# aq_mx_v1-4-0c.net
KiCad netlist of a schematic drawn in EAGLE
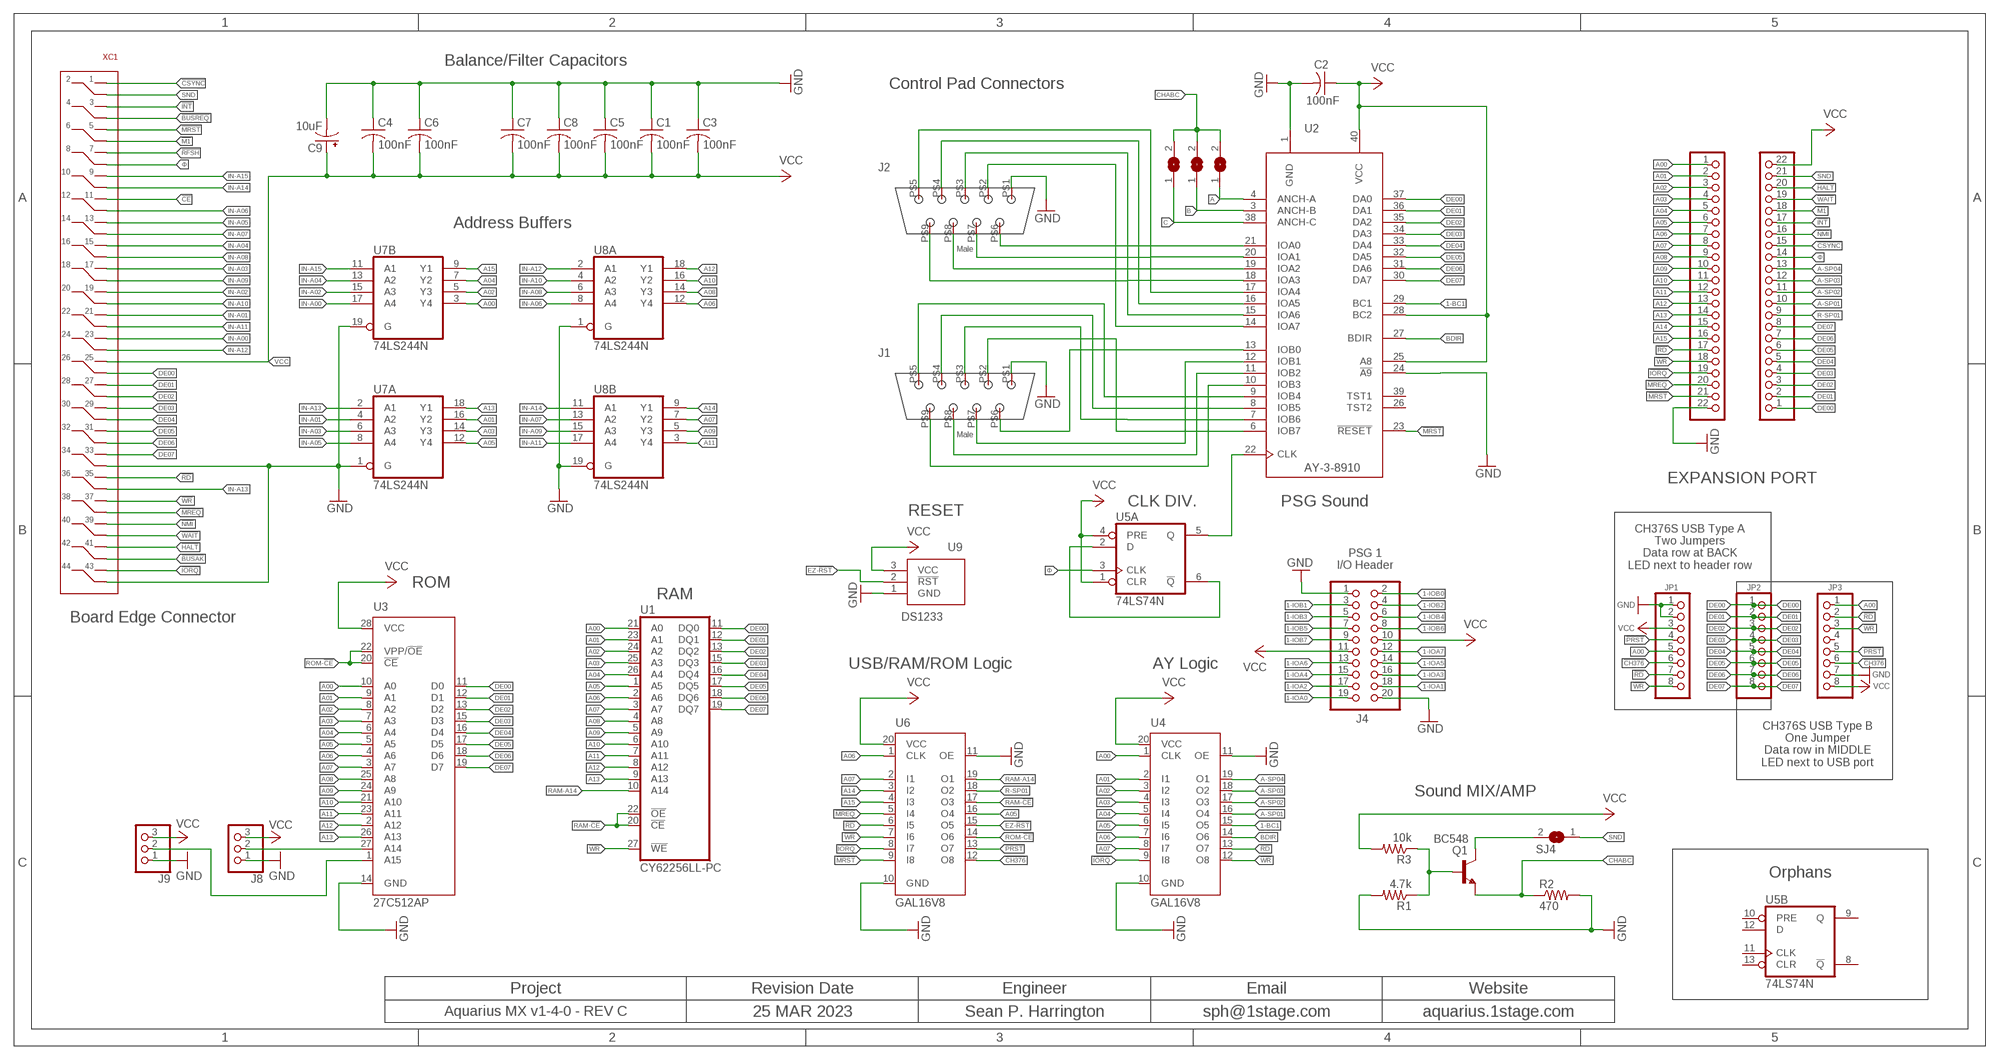
[diagram p0: schematic, sheet 1]

(export (version "E")
  (design (tool "Eeschema 10.0.6"))
  (components
    (comp (ref "C1")
      (value "100nF")
      (footprint "eagle-import:C050-025X075")
      (libsource (lib "eagle-import") (part "C-US050-025X075"))
    )
    (comp (ref "C2")
      (value "100nF")
      (footprint "eagle-import:C050-025X075")
      (libsource (lib "eagle-import") (part "C-US050-025X075"))
    )
    (comp (ref "C3")
      (value "100nF")
      (footprint "eagle-import:C050-025X075")
      (libsource (lib "eagle-import") (part "C-US050-025X075"))
    )
    (comp (ref "C4")
      (value "100nF")
      (footprint "eagle-import:C050-025X075")
      (libsource (lib "eagle-import") (part "C-US050-025X075"))
    )
    (comp (ref "C5")
      (value "100nF")
      (footprint "eagle-import:C050-025X075")
      (libsource (lib "eagle-import") (part "C-US050-025X075"))
    )
    (comp (ref "C6")
      (value "100nF")
      (footprint "eagle-import:C050-025X075")
      (libsource (lib "eagle-import") (part "C-US050-025X075"))
    )
    (comp (ref "C7")
      (value "100nF")
      (footprint "eagle-import:C050-025X075")
      (libsource (lib "eagle-import") (part "C-US050-025X075"))
    )
    (comp (ref "C8")
      (value "100nF")
      (footprint "eagle-import:C050-025X075")
      (libsource (lib "eagle-import") (part "C-US050-025X075"))
    )
    (comp (ref "C9")
      (value "10uF")
      (footprint "eagle-import:E22-6")
      (libsource (lib "eagle-import") (part "CPOL-USE22-6AXIAL"))
    )
    (comp (ref "J1")
      (value "DB9-MALE-RA")
      (footprint "eagle-import:DB9-MALE-RA")
      (libsource (lib "eagle-import") (part "DB9-MALE-RA"))
    )
    (comp (ref "J2")
      (value "DB9-MALE-RA")
      (footprint "eagle-import:DB9-MALE-RA")
      (libsource (lib "eagle-import") (part "DB9-MALE-RA"))
    )
    (comp (ref "J4")
      (value "PINHD-2X10")
      (footprint "eagle-import:2X10")
      (libsource (lib "eagle-import") (part "PINHD-2X10"))
    )
    (comp (ref "J6")
      (value "PINHD-1X22")
      (footprint "eagle-import:1X22")
      (libsource (lib "eagle-import") (part "PINHD-1X22"))
    )
    (comp (ref "J7")
      (value "PINHD-1X22")
      (footprint "eagle-import:1X22")
      (libsource (lib "eagle-import") (part "PINHD-1X22"))
    )
    (comp (ref "J8")
      (value "PINHD-1X3")
      (footprint "eagle-import:1X03")
      (libsource (lib "eagle-import") (part "PINHD-1X3"))
    )
    (comp (ref "J9")
      (value "PINHD-1X3")
      (footprint "eagle-import:1X03")
      (libsource (lib "eagle-import") (part "PINHD-1X3"))
    )
    (comp (ref "JP1")
      (value "PINHD-1X8")
      (footprint "eagle-import:1X08")
      (libsource (lib "eagle-import") (part "PINHD-1X8"))
    )
    (comp (ref "JP2")
      (value "PINHD-1X8")
      (footprint "eagle-import:1X08")
      (libsource (lib "eagle-import") (part "PINHD-1X8"))
    )
    (comp (ref "JP3")
      (value "PINHD-1X8")
      (footprint "eagle-import:1X08")
      (libsource (lib "eagle-import") (part "PINHD-1X8"))
    )
    (comp (ref "Q1")
      (value "BC548")
      (footprint "eagle-import:TO92-CBE")
      (libsource (lib "eagle-import") (part "-NPN-TO92-CBEBC548"))
    )
    (comp (ref "R1")
      (value "4.7k")
      (footprint "eagle-import:0204_7")
      (libsource (lib "eagle-import") (part "R-US_0204/7"))
    )
    (comp (ref "R2")
      (value "470")
      (footprint "eagle-import:0204_7")
      (libsource (lib "eagle-import") (part "R-US_0204/7"))
    )
    (comp (ref "R3")
      (value "10k")
      (footprint "eagle-import:0204_7")
      (libsource (lib "eagle-import") (part "R-US_0204/7"))
    )
    (comp (ref "SJ1") (value "SJ") (footprint "eagle-import:SJ") (libsource (lib "eagle-import") (part "SJ")))
    (comp (ref "SJ2") (value "SJ") (footprint "eagle-import:SJ") (libsource (lib "eagle-import") (part "SJ")))
    (comp (ref "SJ3") (value "SJ") (footprint "eagle-import:SJ") (libsource (lib "eagle-import") (part "SJ")))
    (comp (ref "SJ4") (value "SJ") (footprint "eagle-import:SJ") (libsource (lib "eagle-import") (part "SJ")))
    (comp (ref "U1")
      (value "CY62256LL-PC")
      (footprint "eagle-import:DIL28-6")
      (libsource (lib "eagle-import") (part "CY62256LL-?PC"))
    )
    (comp (ref "U2")
      (value "AY-3-8910")
      (footprint "eagle-import:RAD38910-DIL40-6")
      (libsource (lib "eagle-import") (part "RAD38910DIL40-6"))
    )
    (comp (ref "U3")
      (value "27C512AP")
      (footprint "eagle-import:DIL28-6")
      (fields (field (name "MPN") "M27C512-90B6"))
      (libsource (lib "eagle-import") (part "27512APC"))
    )
    (comp (ref "U4")
      (value "GAL16V8")
      (footprint "eagle-import:DIL20")
      (fields (field (name "MPN") "ATF16V8CZ-15PU"))
      (libsource (lib "eagle-import") (part "ATF16V8BP3"))
    )
    (comp (ref "U5")
      (value "74LS74N")
      (footprint "eagle-import:DIL14")
      (libsource (lib "eagle-import") (part "7474NLS"))
    )
    (comp (ref "U6")
      (value "GAL16V8")
      (footprint "eagle-import:DIL20")
      (fields (field (name "MPN") "ATF16V8CZ-15PU"))
      (libsource (lib "eagle-import") (part "ATF16V8BP3"))
    )
    (comp (ref "U7")
      (value "74LS244N")
      (footprint "eagle-import:DIL20")
      (libsource (lib "eagle-import") (part "74244NLS"))
    )
    (comp (ref "U8")
      (value "74LS244N")
      (footprint "eagle-import:DIL20")
      (libsource (lib "eagle-import") (part "74244NLS"))
    )
    (comp (ref "U9")
      (value "DS1233")
      (footprint "eagle-import:TO-92")
      (fields
        (field (name "ARROW_PART_NUMBER") "DS1233-10+")
        (field (name "MOUSER_PART_NUMBER") "700-DS1233-10")
      )
      (libsource (lib "eagle-import") (part "DS1233-10+"))
    )
    (comp (ref "XC1")
      (value "AQ-CART-EDGE")
      (footprint "eagle-import:AQ-CART-EDGE")
      (libsource (lib "eagle-import") (part "AQ-CART-EDGE"))
    )
  )
  (nets
    (net (code "1") (name "/EZ-~{RST}") (class "Default")
      (node (ref "U6") (pin "15") (pinfunction "O5_15") (pintype "output"))
      (node (ref "U9") (pin "2") (pinfunction "~{RST}_2") (pintype "input"))
    )
    (net (code "2") (name "/RAM-~{CE}") (class "Default")
      (node (ref "U1") (pin "20") (pinfunction "~{CE}_20") (pintype "input"))
      (node (ref "U1") (pin "22") (pinfunction "~{OE}_22") (pintype "input"))
      (node (ref "U6") (pin "17") (pinfunction "O3_17") (pintype "output"))
    )
    (net (code "3") (name "/ROM-~{CE}") (class "Default")
      (node (ref "U3") (pin "20") (pinfunction "~{CE}_20") (pintype "input"))
      (node (ref "U3") (pin "22") (pinfunction "VPP/~{OE}_22") (pintype "input"))
      (node (ref "U6") (pin "14") (pinfunction "O6_14") (pintype "output"))
    )
    (net (code "4") (name "/~{BUSAK}") (class "Default")
      (node (ref "XC1") (pin "P$42") (pinfunction "X42_P$42") (pintype "bidirectional"))
    )
    (net (code "5") (name "/~{BUSREQ}") (class "Default")
      (node (ref "XC1") (pin "P$4") (pinfunction "X4_P$4") (pintype "bidirectional"))
    )
    (net (code "6") (name "/~{CE}") (class "Default")
      (node (ref "XC1") (pin "P$11") (pinfunction "X11_P$11") (pintype "bidirectional"))
    )
    (net (code "7") (name "/~{CH376}") (class "Default")
      (node (ref "JP1") (pin "6") (pinfunction "6_6") (pintype "passive"))
      (node (ref "JP3") (pin "6") (pinfunction "6_6") (pintype "passive"))
      (node (ref "U6") (pin "12") (pinfunction "O8_12") (pintype "output"))
    )
    (net (code "8") (name "/~{CSYNC}") (class "Default")
      (node (ref "J6") (pin "15") (pinfunction "15_15") (pintype "passive"))
      (node (ref "XC1") (pin "P$1") (pinfunction "X1_P$1") (pintype "bidirectional"))
    )
    (net (code "9") (name "/~{HALT}") (class "Default")
      (node (ref "J6") (pin "20") (pinfunction "20_20") (pintype "passive"))
      (node (ref "XC1") (pin "P$41") (pinfunction "X41_P$41") (pintype "bidirectional"))
    )
    (net (code "10") (name "/~{INT}") (class "Default")
      (node (ref "J6") (pin "17") (pinfunction "17_17") (pintype "passive"))
      (node (ref "XC1") (pin "P$3") (pinfunction "X3_P$3") (pintype "bidirectional"))
    )
    (net (code "11") (name "/~{IORQ}") (class "Default")
      (node (ref "J7") (pin "19") (pinfunction "19_19") (pintype "passive"))
      (node (ref "U4") (pin "9") (pinfunction "I8_9") (pintype "input"))
      (node (ref "U6") (pin "8") (pinfunction "I7_8") (pintype "input"))
      (node (ref "XC1") (pin "P$43") (pinfunction "X43_P$43") (pintype "bidirectional"))
    )
    (net (code "12") (name "/~{M1}") (class "Default")
      (node (ref "J6") (pin "18") (pinfunction "18_18") (pintype "passive"))
      (node (ref "XC1") (pin "P$6") (pinfunction "X6_P$6") (pintype "bidirectional"))
    )
    (net (code "13") (name "/~{MREQ}") (class "Default")
      (node (ref "J7") (pin "20") (pinfunction "20_20") (pintype "passive"))
      (node (ref "U6") (pin "5") (pinfunction "I4_5") (pintype "input"))
      (node (ref "XC1") (pin "P$38") (pinfunction "X38_P$38") (pintype "bidirectional"))
    )
    (net (code "14") (name "/~{MRST}") (class "Default")
      (node (ref "J7") (pin "21") (pinfunction "21_21") (pintype "passive"))
      (node (ref "U2") (pin "23") (pinfunction "~{RESET}_23") (pintype "bidirectional"))
      (node (ref "U6") (pin "9") (pinfunction "I8_9") (pintype "input"))
      (node (ref "XC1") (pin "P$5") (pinfunction "X5_P$5") (pintype "bidirectional"))
    )
    (net (code "15") (name "/~{NMI}") (class "Default")
      (node (ref "J6") (pin "16") (pinfunction "16_16") (pintype "passive"))
      (node (ref "XC1") (pin "P$39") (pinfunction "X39_P$39") (pintype "bidirectional"))
    )
    (net (code "16") (name "/~{PRST}") (class "Default")
      (node (ref "JP1") (pin "4") (pinfunction "4_4") (pintype "passive"))
      (node (ref "JP3") (pin "5") (pinfunction "5_5") (pintype "passive"))
      (node (ref "U6") (pin "13") (pinfunction "O7_13") (pintype "output"))
    )
    (net (code "17") (name "/~{RD}") (class "Default")
      (node (ref "J7") (pin "17") (pinfunction "17_17") (pintype "passive"))
      (node (ref "JP1") (pin "7") (pinfunction "7_7") (pintype "passive"))
      (node (ref "JP3") (pin "2") (pinfunction "2_2") (pintype "passive"))
      (node (ref "U4") (pin "13") (pinfunction "O7_13") (pintype "output"))
      (node (ref "U6") (pin "6") (pinfunction "I5_6") (pintype "input"))
      (node (ref "XC1") (pin "P$35") (pinfunction "X35_P$35") (pintype "bidirectional"))
    )
    (net (code "18") (name "/~{RFSH}") (class "Default")
      (node (ref "XC1") (pin "P$7") (pinfunction "X7_P$7") (pintype "bidirectional"))
    )
    (net (code "19") (name "/~{WAIT}") (class "Default")
      (node (ref "J6") (pin "19") (pinfunction "19_19") (pintype "passive"))
      (node (ref "XC1") (pin "P$40") (pinfunction "X40_P$40") (pintype "bidirectional"))
    )
    (net (code "20") (name "/~{WR}") (class "Default")
      (node (ref "J7") (pin "18") (pinfunction "18_18") (pintype "passive"))
      (node (ref "JP1") (pin "8") (pinfunction "8_8") (pintype "passive"))
      (node (ref "JP3") (pin "3") (pinfunction "3_3") (pintype "passive"))
      (node (ref "U1") (pin "27") (pinfunction "~{WE}_27") (pintype "input"))
      (node (ref "U4") (pin "12") (pinfunction "O8_12") (pintype "output"))
      (node (ref "U6") (pin "7") (pinfunction "I6_7") (pintype "input"))
      (node (ref "XC1") (pin "P$37") (pinfunction "X37_P$37") (pintype "bidirectional"))
    )
    (net (code "21") (name "1-BC1") (class "Default")
      (node (ref "U2") (pin "29") (pinfunction "BC1_29") (pintype "bidirectional"))
      (node (ref "U4") (pin "15") (pinfunction "O5_15") (pintype "output"))
    )
    (net (code "22") (name "1-IOA0") (class "Default")
      (node (ref "J2") (pin "P$6") (pinfunction "P$6_P$6") (pintype "bidirectional"))
      (node (ref "J4") (pin "19") (pinfunction "19_19") (pintype "passive"))
      (node (ref "U2") (pin "21") (pinfunction "IOA0_21") (pintype "bidirectional"))
    )
    (net (code "23") (name "1-IOA1") (class "Default")
      (node (ref "J2") (pin "P$7") (pinfunction "P$7_P$7") (pintype "bidirectional"))
      (node (ref "J4") (pin "18") (pinfunction "18_18") (pintype "passive"))
      (node (ref "U2") (pin "20") (pinfunction "IOA1_20") (pintype "bidirectional"))
    )
    (net (code "24") (name "1-IOA2") (class "Default")
      (node (ref "J2") (pin "P$8") (pinfunction "P$8_P$8") (pintype "bidirectional"))
      (node (ref "J4") (pin "17") (pinfunction "17_17") (pintype "passive"))
      (node (ref "U2") (pin "19") (pinfunction "IOA2_19") (pintype "bidirectional"))
    )
    (net (code "25") (name "1-IOA3") (class "Default")
      (node (ref "J2") (pin "P$9") (pinfunction "P$9_P$9") (pintype "bidirectional"))
      (node (ref "J4") (pin "16") (pinfunction "16_16") (pintype "passive"))
      (node (ref "U2") (pin "18") (pinfunction "IOA3_18") (pintype "bidirectional"))
    )
    (net (code "26") (name "1-IOA4") (class "Default")
      (node (ref "J2") (pin "P$5") (pinfunction "P$5_P$5") (pintype "bidirectional"))
      (node (ref "J4") (pin "15") (pinfunction "15_15") (pintype "passive"))
      (node (ref "U2") (pin "17") (pinfunction "IOA4_17") (pintype "bidirectional"))
    )
    (net (code "27") (name "1-IOA5") (class "Default")
      (node (ref "J2") (pin "P$4") (pinfunction "P$4_P$4") (pintype "bidirectional"))
      (node (ref "J4") (pin "14") (pinfunction "14_14") (pintype "passive"))
      (node (ref "U2") (pin "16") (pinfunction "IOA5_16") (pintype "bidirectional"))
    )
    (net (code "28") (name "1-IOA6") (class "Default")
      (node (ref "J2") (pin "P$3") (pinfunction "P$3_P$3") (pintype "bidirectional"))
      (node (ref "J4") (pin "13") (pinfunction "13_13") (pintype "passive"))
      (node (ref "U2") (pin "15") (pinfunction "IOA6_15") (pintype "bidirectional"))
    )
    (net (code "29") (name "1-IOA7") (class "Default")
      (node (ref "J2") (pin "P$2") (pinfunction "P$2_P$2") (pintype "bidirectional"))
      (node (ref "J4") (pin "12") (pinfunction "12_12") (pintype "passive"))
      (node (ref "U2") (pin "14") (pinfunction "IOA7_14") (pintype "bidirectional"))
    )
    (net (code "30") (name "1-IOB0") (class "Default")
      (node (ref "J1") (pin "P$6") (pinfunction "P$6_P$6") (pintype "bidirectional"))
      (node (ref "J4") (pin "2") (pinfunction "2_2") (pintype "passive"))
      (node (ref "U2") (pin "13") (pinfunction "IOB0_13") (pintype "bidirectional"))
    )
    (net (code "31") (name "1-IOB1") (class "Default")
      (node (ref "J1") (pin "P$7") (pinfunction "P$7_P$7") (pintype "bidirectional"))
      (node (ref "J4") (pin "3") (pinfunction "3_3") (pintype "passive"))
      (node (ref "U2") (pin "12") (pinfunction "IOB1_12") (pintype "bidirectional"))
    )
    (net (code "32") (name "1-IOB2") (class "Default")
      (node (ref "J1") (pin "P$8") (pinfunction "P$8_P$8") (pintype "bidirectional"))
      (node (ref "J4") (pin "4") (pinfunction "4_4") (pintype "passive"))
      (node (ref "U2") (pin "11") (pinfunction "IOB2_11") (pintype "bidirectional"))
    )
    (net (code "33") (name "1-IOB3") (class "Default")
      (node (ref "J1") (pin "P$9") (pinfunction "P$9_P$9") (pintype "bidirectional"))
      (node (ref "J4") (pin "5") (pinfunction "5_5") (pintype "passive"))
      (node (ref "U2") (pin "10") (pinfunction "IOB3_10") (pintype "bidirectional"))
    )
    (net (code "34") (name "1-IOB4") (class "Default")
      (node (ref "J1") (pin "P$5") (pinfunction "P$5_P$5") (pintype "bidirectional"))
      (node (ref "J4") (pin "6") (pinfunction "6_6") (pintype "passive"))
      (node (ref "U2") (pin "9") (pinfunction "IOB4_9") (pintype "bidirectional"))
    )
    (net (code "35") (name "1-IOB5") (class "Default")
      (node (ref "J1") (pin "P$4") (pinfunction "P$4_P$4") (pintype "bidirectional"))
      (node (ref "J4") (pin "7") (pinfunction "7_7") (pintype "passive"))
      (node (ref "U2") (pin "8") (pinfunction "IOB5_8") (pintype "bidirectional"))
    )
    (net (code "36") (name "1-IOB6") (class "Default")
      (node (ref "J1") (pin "P$3") (pinfunction "P$3_P$3") (pintype "bidirectional"))
      (node (ref "J4") (pin "8") (pinfunction "8_8") (pintype "passive"))
      (node (ref "U2") (pin "7") (pinfunction "IOB6_7") (pintype "bidirectional"))
    )
    (net (code "37") (name "1-IOB7") (class "Default")
      (node (ref "J1") (pin "P$2") (pinfunction "P$2_P$2") (pintype "bidirectional"))
      (node (ref "J4") (pin "9") (pinfunction "9_9") (pintype "passive"))
      (node (ref "U2") (pin "6") (pinfunction "IOB7_6") (pintype "bidirectional"))
    )
    (net (code "38") (name "A") (class "Default")
      (node (ref "SJ1") (pin "1") (pinfunction "1_1") (pintype "passive"))
      (node (ref "U2") (pin "4") (pinfunction "ANCH-A_4") (pintype "bidirectional"))
    )
    (net (code "39") (name "A-SP01") (class "Default")
      (node (ref "J6") (pin "10") (pinfunction "10_10") (pintype "passive"))
      (node (ref "U4") (pin "16") (pinfunction "O4_16") (pintype "output"))
    )
    (net (code "40") (name "A-SP02") (class "Default")
      (node (ref "J6") (pin "11") (pinfunction "11_11") (pintype "passive"))
      (node (ref "U4") (pin "17") (pinfunction "O3_17") (pintype "output"))
    )
    (net (code "41") (name "A-SP03") (class "Default")
      (node (ref "J6") (pin "12") (pinfunction "12_12") (pintype "passive"))
      (node (ref "U4") (pin "18") (pinfunction "O2_18") (pintype "output"))
    )
    (net (code "42") (name "A-SP04") (class "Default")
      (node (ref "J6") (pin "13") (pinfunction "13_13") (pintype "passive"))
      (node (ref "U4") (pin "19") (pinfunction "O1_19") (pintype "output"))
    )
    (net (code "43") (name "A00") (class "Default")
      (node (ref "J7") (pin "1") (pinfunction "1_1") (pintype "passive"))
      (node (ref "JP1") (pin "5") (pinfunction "5_5") (pintype "passive"))
      (node (ref "JP3") (pin "1") (pinfunction "1_1") (pintype "passive"))
      (node (ref "U1") (pin "21") (pinfunction "A0_21") (pintype "input"))
      (node (ref "U3") (pin "10") (pinfunction "A0_10") (pintype "input"))
      (node (ref "U4") (pin "1") (pinfunction "CLK_1") (pintype "input"))
      (node (ref "U7") (pin "3") (pinfunction "Y4_3") (pintype "tri_state"))
    )
    (net (code "44") (name "A01") (class "Default")
      (node (ref "J7") (pin "2") (pinfunction "2_2") (pintype "passive"))
      (node (ref "U1") (pin "23") (pinfunction "A1_23") (pintype "input"))
      (node (ref "U3") (pin "9") (pinfunction "A1_9") (pintype "input"))
      (node (ref "U4") (pin "2") (pinfunction "I1_2") (pintype "input"))
      (node (ref "U7") (pin "16") (pinfunction "Y2_16") (pintype "tri_state"))
    )
    (net (code "45") (name "A02") (class "Default")
      (node (ref "J7") (pin "3") (pinfunction "3_3") (pintype "passive"))
      (node (ref "U1") (pin "24") (pinfunction "A2_24") (pintype "input"))
      (node (ref "U3") (pin "8") (pinfunction "A2_8") (pintype "input"))
      (node (ref "U4") (pin "3") (pinfunction "I2_3") (pintype "input"))
      (node (ref "U7") (pin "5") (pinfunction "Y3_5") (pintype "tri_state"))
    )
    (net (code "46") (name "A03") (class "Default")
      (node (ref "J7") (pin "4") (pinfunction "4_4") (pintype "passive"))
      (node (ref "U1") (pin "25") (pinfunction "A3_25") (pintype "input"))
      (node (ref "U3") (pin "7") (pinfunction "A3_7") (pintype "input"))
      (node (ref "U4") (pin "4") (pinfunction "I3_4") (pintype "input"))
      (node (ref "U7") (pin "14") (pinfunction "Y3_14") (pintype "tri_state"))
    )
    (net (code "47") (name "A04") (class "Default")
      (node (ref "J7") (pin "5") (pinfunction "5_5") (pintype "passive"))
      (node (ref "U1") (pin "26") (pinfunction "A4_26") (pintype "input"))
      (node (ref "U3") (pin "6") (pinfunction "A4_6") (pintype "input"))
      (node (ref "U4") (pin "5") (pinfunction "I4_5") (pintype "input"))
      (node (ref "U7") (pin "7") (pinfunction "Y2_7") (pintype "tri_state"))
    )
    (net (code "48") (name "A05") (class "Default")
      (node (ref "J7") (pin "6") (pinfunction "6_6") (pintype "passive"))
      (node (ref "U1") (pin "1") (pinfunction "A5_1") (pintype "input"))
      (node (ref "U3") (pin "5") (pinfunction "A5_5") (pintype "input"))
      (node (ref "U4") (pin "6") (pinfunction "I5_6") (pintype "input"))
      (node (ref "U6") (pin "16") (pinfunction "O4_16") (pintype "output"))
      (node (ref "U7") (pin "12") (pinfunction "Y4_12") (pintype "tri_state"))
    )
    (net (code "49") (name "A06") (class "Default")
      (node (ref "J7") (pin "7") (pinfunction "7_7") (pintype "passive"))
      (node (ref "U1") (pin "2") (pinfunction "A6_2") (pintype "input"))
      (node (ref "U3") (pin "4") (pinfunction "A6_4") (pintype "input"))
      (node (ref "U4") (pin "7") (pinfunction "I6_7") (pintype "input"))
      (node (ref "U6") (pin "1") (pinfunction "CLK_1") (pintype "input"))
      (node (ref "U8") (pin "12") (pinfunction "Y4_12") (pintype "tri_state"))
    )
    (net (code "50") (name "A07") (class "Default")
      (node (ref "J7") (pin "8") (pinfunction "8_8") (pintype "passive"))
      (node (ref "U1") (pin "3") (pinfunction "A7_3") (pintype "input"))
      (node (ref "U3") (pin "3") (pinfunction "A7_3") (pintype "input"))
      (node (ref "U4") (pin "8") (pinfunction "I7_8") (pintype "input"))
      (node (ref "U6") (pin "2") (pinfunction "I1_2") (pintype "input"))
      (node (ref "U8") (pin "7") (pinfunction "Y2_7") (pintype "tri_state"))
    )
    (net (code "51") (name "A08") (class "Default")
      (node (ref "J7") (pin "9") (pinfunction "9_9") (pintype "passive"))
      (node (ref "U1") (pin "4") (pinfunction "A8_4") (pintype "input"))
      (node (ref "U3") (pin "25") (pinfunction "A8_25") (pintype "input"))
      (node (ref "U8") (pin "14") (pinfunction "Y3_14") (pintype "tri_state"))
    )
    (net (code "52") (name "A09") (class "Default")
      (node (ref "J7") (pin "10") (pinfunction "10_10") (pintype "passive"))
      (node (ref "U1") (pin "5") (pinfunction "A9_5") (pintype "input"))
      (node (ref "U3") (pin "24") (pinfunction "A9_24") (pintype "input"))
      (node (ref "U8") (pin "5") (pinfunction "Y3_5") (pintype "tri_state"))
    )
    (net (code "53") (name "A10") (class "Default")
      (node (ref "J7") (pin "11") (pinfunction "11_11") (pintype "passive"))
      (node (ref "U1") (pin "6") (pinfunction "A10_6") (pintype "input"))
      (node (ref "U3") (pin "21") (pinfunction "A10_21") (pintype "input"))
      (node (ref "U8") (pin "16") (pinfunction "Y2_16") (pintype "tri_state"))
    )
    (net (code "54") (name "A11") (class "Default")
      (node (ref "J7") (pin "12") (pinfunction "12_12") (pintype "passive"))
      (node (ref "U1") (pin "7") (pinfunction "A11_7") (pintype "input"))
      (node (ref "U3") (pin "23") (pinfunction "A11_23") (pintype "input"))
      (node (ref "U8") (pin "3") (pinfunction "Y4_3") (pintype "tri_state"))
    )
    (net (code "55") (name "A12") (class "Default")
      (node (ref "J7") (pin "13") (pinfunction "13_13") (pintype "passive"))
      (node (ref "U1") (pin "8") (pinfunction "A12_8") (pintype "input"))
      (node (ref "U3") (pin "2") (pinfunction "A12_2") (pintype "input"))
      (node (ref "U8") (pin "18") (pinfunction "Y1_18") (pintype "tri_state"))
    )
    (net (code "56") (name "A13") (class "Default")
      (node (ref "J7") (pin "14") (pinfunction "14_14") (pintype "passive"))
      (node (ref "U1") (pin "9") (pinfunction "A13_9") (pintype "input"))
      (node (ref "U3") (pin "26") (pinfunction "A13_26") (pintype "input"))
      (node (ref "U7") (pin "18") (pinfunction "Y1_18") (pintype "tri_state"))
    )
    (net (code "57") (name "A14") (class "Default")
      (node (ref "J7") (pin "15") (pinfunction "15_15") (pintype "passive"))
      (node (ref "U6") (pin "3") (pinfunction "I2_3") (pintype "input"))
      (node (ref "U8") (pin "9") (pinfunction "Y1_9") (pintype "tri_state"))
    )
    (net (code "58") (name "A15") (class "Default")
      (node (ref "J7") (pin "16") (pinfunction "16_16") (pintype "passive"))
      (node (ref "U6") (pin "4") (pinfunction "I3_4") (pintype "input"))
      (node (ref "U7") (pin "9") (pinfunction "Y1_9") (pintype "tri_state"))
    )
    (net (code "59") (name "B") (class "Default")
      (node (ref "SJ2") (pin "1") (pinfunction "1_1") (pintype "passive"))
      (node (ref "U2") (pin "3") (pinfunction "ANCH-B_3") (pintype "bidirectional"))
    )
    (net (code "60") (name "BDIR") (class "Default")
      (node (ref "U2") (pin "27") (pinfunction "BDIR_27") (pintype "bidirectional"))
      (node (ref "U4") (pin "14") (pinfunction "O6_14") (pintype "output"))
    )
    (net (code "61") (name "C") (class "Default")
      (node (ref "SJ3") (pin "1") (pinfunction "1_1") (pintype "passive"))
      (node (ref "U2") (pin "38") (pinfunction "ANCH-C_38") (pintype "bidirectional"))
    )
    (net (code "62") (name "CHABC") (class "Default")
      (node (ref "Q1") (pin "E") (pinfunction "E_E") (pintype "passive"))
      (node (ref "R2") (pin "1") (pinfunction "1_1") (pintype "passive"))
      (node (ref "SJ1") (pin "2") (pinfunction "2_2") (pintype "passive"))
      (node (ref "SJ2") (pin "2") (pinfunction "2_2") (pintype "passive"))
      (node (ref "SJ3") (pin "2") (pinfunction "2_2") (pintype "passive"))
    )
    (net (code "63") (name "DE00") (class "Default")
      (node (ref "J6") (pin "1") (pinfunction "1_1") (pintype "passive"))
      (node (ref "JP2") (pin "1") (pinfunction "1_1") (pintype "passive"))
      (node (ref "U1") (pin "11") (pinfunction "DQ0_11") (pintype "bidirectional"))
      (node (ref "U2") (pin "37") (pinfunction "DA0_37") (pintype "bidirectional"))
      (node (ref "U3") (pin "11") (pinfunction "D0_11") (pintype "tri_state"))
      (node (ref "XC1") (pin "P$26") (pinfunction "X26_P$26") (pintype "bidirectional"))
    )
    (net (code "64") (name "DE01") (class "Default")
      (node (ref "J6") (pin "2") (pinfunction "2_2") (pintype "passive"))
      (node (ref "JP2") (pin "2") (pinfunction "2_2") (pintype "passive"))
      (node (ref "U1") (pin "12") (pinfunction "DQ1_12") (pintype "bidirectional"))
      (node (ref "U2") (pin "36") (pinfunction "DA1_36") (pintype "bidirectional"))
      (node (ref "U3") (pin "12") (pinfunction "D1_12") (pintype "tri_state"))
      (node (ref "XC1") (pin "P$27") (pinfunction "X27_P$27") (pintype "bidirectional"))
    )
    (net (code "65") (name "DE02") (class "Default")
      (node (ref "J6") (pin "3") (pinfunction "3_3") (pintype "passive"))
      (node (ref "JP2") (pin "3") (pinfunction "3_3") (pintype "passive"))
      (node (ref "U1") (pin "13") (pinfunction "DQ2_13") (pintype "bidirectional"))
      (node (ref "U2") (pin "35") (pinfunction "DA2_35") (pintype "bidirectional"))
      (node (ref "U3") (pin "13") (pinfunction "D2_13") (pintype "tri_state"))
      (node (ref "XC1") (pin "P$28") (pinfunction "X28_P$28") (pintype "bidirectional"))
    )
    (net (code "66") (name "DE03") (class "Default")
      (node (ref "J6") (pin "4") (pinfunction "4_4") (pintype "passive"))
      (node (ref "JP2") (pin "4") (pinfunction "4_4") (pintype "passive"))
      (node (ref "U1") (pin "15") (pinfunction "DQ3_15") (pintype "bidirectional"))
      (node (ref "U2") (pin "34") (pinfunction "DA3_34") (pintype "bidirectional"))
      (node (ref "U3") (pin "15") (pinfunction "D3_15") (pintype "tri_state"))
      (node (ref "XC1") (pin "P$29") (pinfunction "X29_P$29") (pintype "bidirectional"))
    )
    (net (code "67") (name "DE04") (class "Default")
      (node (ref "J6") (pin "5") (pinfunction "5_5") (pintype "passive"))
      (node (ref "JP2") (pin "5") (pinfunction "5_5") (pintype "passive"))
      (node (ref "U1") (pin "16") (pinfunction "DQ4_16") (pintype "bidirectional"))
      (node (ref "U2") (pin "33") (pinfunction "DA4_33") (pintype "bidirectional"))
      (node (ref "U3") (pin "16") (pinfunction "D4_16") (pintype "tri_state"))
      (node (ref "XC1") (pin "P$30") (pinfunction "X30_P$30") (pintype "bidirectional"))
    )
    (net (code "68") (name "DE05") (class "Default")
      (node (ref "J6") (pin "6") (pinfunction "6_6") (pintype "passive"))
      (node (ref "JP2") (pin "6") (pinfunction "6_6") (pintype "passive"))
      (node (ref "U1") (pin "17") (pinfunction "DQ5_17") (pintype "bidirectional"))
      (node (ref "U2") (pin "32") (pinfunction "DA5_32") (pintype "bidirectional"))
      (node (ref "U3") (pin "17") (pinfunction "D5_17") (pintype "tri_state"))
      (node (ref "XC1") (pin "P$31") (pinfunction "X31_P$31") (pintype "bidirectional"))
    )
    (net (code "69") (name "DE06") (class "Default")
      (node (ref "J6") (pin "7") (pinfunction "7_7") (pintype "passive"))
      (node (ref "JP2") (pin "7") (pinfunction "7_7") (pintype "passive"))
      (node (ref "U1") (pin "18") (pinfunction "DQ6_18") (pintype "bidirectional"))
      (node (ref "U2") (pin "31") (pinfunction "DA6_31") (pintype "bidirectional"))
      (node (ref "U3") (pin "18") (pinfunction "D6_18") (pintype "tri_state"))
      (node (ref "XC1") (pin "P$32") (pinfunction "X32_P$32") (pintype "bidirectional"))
    )
    (net (code "70") (name "DE07") (class "Default")
      (node (ref "J6") (pin "8") (pinfunction "8_8") (pintype "passive"))
      (node (ref "JP2") (pin "8") (pinfunction "8_8") (pintype "passive"))
      (node (ref "U1") (pin "19") (pinfunction "DQ7_19") (pintype "bidirectional"))
      (node (ref "U2") (pin "30") (pinfunction "DA7_30") (pintype "bidirectional"))
      (node (ref "U3") (pin "19") (pinfunction "D7_19") (pintype "tri_state"))
      (node (ref "XC1") (pin "P$33") (pinfunction "X33_P$33") (pintype "bidirectional"))
    )
    (net (code "71") (name "GND") (class "Default")
      (node (ref "C1") (pin "1") (pinfunction "1_1") (pintype "passive"))
      (node (ref "C2") (pin "2") (pinfunction "2_2") (pintype "passive"))
      (node (ref "C3") (pin "1") (pinfunction "1_1") (pintype "passive"))
      (node (ref "C4") (pin "1") (pinfunction "1_1") (pintype "passive"))
      (node (ref "C5") (pin "1") (pinfunction "1_1") (pintype "passive"))
      (node (ref "C6") (pin "1") (pinfunction "1_1") (pintype "passive"))
      (node (ref "C7") (pin "1") (pinfunction "1_1") (pintype "passive"))
      (node (ref "C8") (pin "1") (pinfunction "1_1") (pintype "passive"))
      (node (ref "C9") (pin "-") (pinfunction "-_-") (pintype "passive"))
      (node (ref "J1") (pin "P$1") (pinfunction "P$1_P$1") (pintype "bidirectional"))
      (node (ref "J2") (pin "P$1") (pinfunction "P$1_P$1") (pintype "bidirectional"))
      (node (ref "J4") (pin "1") (pinfunction "1_1") (pintype "passive"))
      (node (ref "J4") (pin "20") (pinfunction "20_20") (pintype "passive"))
      (node (ref "J7") (pin "22") (pinfunction "22_22") (pintype "passive"))
      (node (ref "J8") (pin "1") (pinfunction "1_1") (pintype "passive"))
      (node (ref "J9") (pin "1") (pinfunction "1_1") (pintype "passive"))
      (node (ref "JP1") (pin "1") (pinfunction "1_1") (pintype "passive"))
      (node (ref "JP1") (pin "2") (pinfunction "2_2") (pintype "passive"))
      (node (ref "JP3") (pin "7") (pinfunction "7_7") (pintype "passive"))
      (node (ref "R1") (pin "2") (pinfunction "2_2") (pintype "passive"))
      (node (ref "R2") (pin "2") (pinfunction "2_2") (pintype "passive"))
      (node (ref "U2") (pin "1") (pinfunction "GND_1") (pintype "power_in"))
      (node (ref "U2") (pin "24") (pinfunction "~{A9}_24") (pintype "bidirectional"))
      (node (ref "U3") (pin "14") (pinfunction "GND_14") (pintype "power_in"))
      (node (ref "U4") (pin "10") (pinfunction "GND_10") (pintype "power_in"))
      (node (ref "U4") (pin "11") (pinfunction "OE_11") (pintype "input"))
      (node (ref "U6") (pin "10") (pinfunction "GND_10") (pintype "power_in"))
      (node (ref "U6") (pin "11") (pinfunction "OE_11") (pintype "input"))
      (node (ref "U7") (pin "1") (pinfunction "G_1") (pintype "input"))
      (node (ref "U7") (pin "19") (pinfunction "G_19") (pintype "input"))
      (node (ref "U8") (pin "1") (pinfunction "G_1") (pintype "input"))
      (node (ref "U8") (pin "19") (pinfunction "G_19") (pintype "input"))
      (node (ref "U9") (pin "1") (pinfunction "GND_1") (pintype "power_in"))
      (node (ref "XC1") (pin "P$34") (pinfunction "X34_P$34") (pintype "bidirectional"))
      (node (ref "XC1") (pin "P$44") (pinfunction "X44_P$44") (pintype "bidirectional"))
    )
    (net (code "72") (name "IN-A00") (class "Default")
      (node (ref "U7") (pin "17") (pinfunction "A4_17") (pintype "input"))
      (node (ref "XC1") (pin "P$23") (pinfunction "X23_P$23") (pintype "bidirectional"))
    )
    (net (code "73") (name "IN-A01") (class "Default")
      (node (ref "U7") (pin "4") (pinfunction "A2_4") (pintype "input"))
      (node (ref "XC1") (pin "P$21") (pinfunction "X21_P$21") (pintype "bidirectional"))
    )
    (net (code "74") (name "IN-A02") (class "Default")
      (node (ref "U7") (pin "15") (pinfunction "A3_15") (pintype "input"))
      (node (ref "XC1") (pin "P$19") (pinfunction "X19_P$19") (pintype "bidirectional"))
    )
    (net (code "75") (name "IN-A03") (class "Default")
      (node (ref "U7") (pin "6") (pinfunction "A3_6") (pintype "input"))
      (node (ref "XC1") (pin "P$17") (pinfunction "X17_P$17") (pintype "bidirectional"))
    )
    (net (code "76") (name "IN-A04") (class "Default")
      (node (ref "U7") (pin "13") (pinfunction "A2_13") (pintype "input"))
      (node (ref "XC1") (pin "P$15") (pinfunction "X15_P$15") (pintype "bidirectional"))
    )
    (net (code "77") (name "IN-A05") (class "Default")
      (node (ref "U7") (pin "8") (pinfunction "A4_8") (pintype "input"))
      (node (ref "XC1") (pin "P$13") (pinfunction "X13_P$13") (pintype "bidirectional"))
    )
    (net (code "78") (name "IN-A06") (class "Default")
      (node (ref "U8") (pin "8") (pinfunction "A4_8") (pintype "input"))
      (node (ref "XC1") (pin "P$12") (pinfunction "X12_P$12") (pintype "bidirectional"))
    )
    (net (code "79") (name "IN-A07") (class "Default")
      (node (ref "U8") (pin "13") (pinfunction "A2_13") (pintype "input"))
      (node (ref "XC1") (pin "P$14") (pinfunction "X14_P$14") (pintype "bidirectional"))
    )
    (net (code "80") (name "IN-A08") (class "Default")
      (node (ref "U8") (pin "6") (pinfunction "A3_6") (pintype "input"))
      (node (ref "XC1") (pin "P$16") (pinfunction "X16_P$16") (pintype "bidirectional"))
    )
    (net (code "81") (name "IN-A09") (class "Default")
      (node (ref "U8") (pin "15") (pinfunction "A3_15") (pintype "input"))
      (node (ref "XC1") (pin "P$18") (pinfunction "X18_P$18") (pintype "bidirectional"))
    )
    (net (code "82") (name "IN-A10") (class "Default")
      (node (ref "U8") (pin "4") (pinfunction "A2_4") (pintype "input"))
      (node (ref "XC1") (pin "P$20") (pinfunction "X20_P$20") (pintype "bidirectional"))
    )
    (net (code "83") (name "IN-A11") (class "Default")
      (node (ref "U8") (pin "17") (pinfunction "A4_17") (pintype "input"))
      (node (ref "XC1") (pin "P$22") (pinfunction "X22_P$22") (pintype "bidirectional"))
    )
    (net (code "84") (name "IN-A12") (class "Default")
      (node (ref "U8") (pin "2") (pinfunction "A1_2") (pintype "input"))
      (node (ref "XC1") (pin "P$24") (pinfunction "X24_P$24") (pintype "bidirectional"))
    )
    (net (code "85") (name "IN-A13") (class "Default")
      (node (ref "U7") (pin "2") (pinfunction "A1_2") (pintype "input"))
      (node (ref "XC1") (pin "P$36") (pinfunction "X36_P$36") (pintype "bidirectional"))
    )
    (net (code "86") (name "IN-A14") (class "Default")
      (node (ref "U8") (pin "11") (pinfunction "A1_11") (pintype "input"))
      (node (ref "XC1") (pin "P$10") (pinfunction "X10_P$10") (pintype "bidirectional"))
    )
    (net (code "87") (name "IN-A15") (class "Default")
      (node (ref "U7") (pin "11") (pinfunction "A1_11") (pintype "input"))
      (node (ref "XC1") (pin "P$9") (pinfunction "X9_P$9") (pintype "bidirectional"))
    )
    (net (code "88") (name "Net-(Q1-PadB)") (class "Default")
      (node (ref "Q1") (pin "B") (pinfunction "B_B") (pintype "passive"))
      (node (ref "R1") (pin "1") (pinfunction "1_1") (pintype "passive"))
      (node (ref "R3") (pin "1") (pinfunction "1_1") (pintype "passive"))
    )
    (net (code "89") (name "Net-(Q1-PadC)") (class "Default")
      (node (ref "Q1") (pin "C") (pinfunction "C_C") (pintype "passive"))
      (node (ref "SJ4") (pin "2") (pinfunction "2_2") (pintype "passive"))
    )
    (net (code "90") (name "Net-(U2-CLK)") (class "Default")
      (node (ref "U2") (pin "22") (pinfunction "CLK_22") (pintype "input"))
      (node (ref "U5") (pin "5") (pinfunction "Q_5") (pintype "output"))
    )
    (net (code "91") (name "Net-(U3-A14)") (class "Default")
      (node (ref "J8") (pin "2") (pinfunction "2_2") (pintype "passive"))
      (node (ref "U3") (pin "27") (pinfunction "A14_27") (pintype "input"))
    )
    (net (code "92") (name "Net-(U3-A15)") (class "Default")
      (node (ref "J9") (pin "2") (pinfunction "2_2") (pintype "passive"))
      (node (ref "U3") (pin "1") (pinfunction "A15_1") (pintype "input"))
    )
    (net (code "93") (name "Net-(U5A-D)") (class "Default")
      (node (ref "U5") (pin "2") (pinfunction "D_2") (pintype "input"))
      (node (ref "U5") (pin "6") (pinfunction "~{Q}_6") (pintype "output"))
    )
    (net (code "94") (name "R-SP01") (class "Default")
      (node (ref "J6") (pin "9") (pinfunction "9_9") (pintype "passive"))
      (node (ref "U6") (pin "18") (pinfunction "O2_18") (pintype "output"))
    )
    (net (code "95") (name "RAM-A14") (class "Default")
      (node (ref "U1") (pin "10") (pinfunction "A14_10") (pintype "input"))
      (node (ref "U6") (pin "19") (pinfunction "O1_19") (pintype "output"))
    )
    (net (code "96") (name "SND") (class "Default")
      (node (ref "J6") (pin "21") (pinfunction "21_21") (pintype "passive"))
      (node (ref "SJ4") (pin "1") (pinfunction "1_1") (pintype "passive"))
      (node (ref "XC1") (pin "P$2") (pinfunction "X2_P$2") (pintype "bidirectional"))
    )
    (net (code "97") (name "VCC") (class "Default")
      (node (ref "C1") (pin "2") (pinfunction "2_2") (pintype "passive"))
      (node (ref "C2") (pin "1") (pinfunction "1_1") (pintype "passive"))
      (node (ref "C3") (pin "2") (pinfunction "2_2") (pintype "passive"))
      (node (ref "C4") (pin "2") (pinfunction "2_2") (pintype "passive"))
      (node (ref "C5") (pin "2") (pinfunction "2_2") (pintype "passive"))
      (node (ref "C6") (pin "2") (pinfunction "2_2") (pintype "passive"))
      (node (ref "C7") (pin "2") (pinfunction "2_2") (pintype "passive"))
      (node (ref "C8") (pin "2") (pinfunction "2_2") (pintype "passive"))
      (node (ref "C9") (pin "+") (pinfunction "+_+") (pintype "passive"))
      (node (ref "J4") (pin "10") (pinfunction "10_10") (pintype "passive"))
      (node (ref "J4") (pin "11") (pinfunction "11_11") (pintype "passive"))
      (node (ref "J6") (pin "22") (pinfunction "22_22") (pintype "passive"))
      (node (ref "J8") (pin "3") (pinfunction "3_3") (pintype "passive"))
      (node (ref "J9") (pin "3") (pinfunction "3_3") (pintype "passive"))
      (node (ref "JP1") (pin "3") (pinfunction "3_3") (pintype "passive"))
      (node (ref "JP3") (pin "8") (pinfunction "8_8") (pintype "passive"))
      (node (ref "R3") (pin "2") (pinfunction "2_2") (pintype "passive"))
      (node (ref "U2") (pin "25") (pinfunction "A8_25") (pintype "bidirectional"))
      (node (ref "U2") (pin "28") (pinfunction "BC2_28") (pintype "bidirectional"))
      (node (ref "U2") (pin "40") (pinfunction "VCC_40") (pintype "power_in"))
      (node (ref "U3") (pin "28") (pinfunction "VCC_28") (pintype "power_in"))
      (node (ref "U4") (pin "20") (pinfunction "VCC_20") (pintype "power_in"))
      (node (ref "U5") (pin "1") (pinfunction "CLR_1") (pintype "input"))
      (node (ref "U5") (pin "4") (pinfunction "PRE_4") (pintype "input"))
      (node (ref "U6") (pin "20") (pinfunction "VCC_20") (pintype "power_in"))
      (node (ref "U9") (pin "3") (pinfunction "VCC_3") (pintype "power_in"))
      (node (ref "XC1") (pin "P$25") (pinfunction "X25_P$25") (pintype "bidirectional"))
    )
    (net (code "98") (name "unconnected-(JP3-Pad4)") (class "Default")
      (node (ref "JP3") (pin "4") (pinfunction "4_4") (pintype "passive"))
    )
    (net (code "99") (name "unconnected-(U2-TST1-Pad39)") (class "Default")
      (node (ref "U2") (pin "39") (pinfunction "TST1_39") (pintype "bidirectional"))
    )
    (net (code "100") (name "unconnected-(U2-TST2-Pad26)") (class "Default")
      (node (ref "U2") (pin "26") (pinfunction "TST2_26") (pintype "bidirectional"))
    )
    (net (code "101") (name "unconnected-(U5B-CLK-Pad11)") (class "Default")
      (node (ref "U5") (pin "11") (pinfunction "CLK_11") (pintype "input"))
    )
    (net (code "102") (name "unconnected-(U5B-CLR-Pad13)") (class "Default")
      (node (ref "U5") (pin "13") (pinfunction "CLR_13") (pintype "input"))
    )
    (net (code "103") (name "unconnected-(U5B-D-Pad12)") (class "Default")
      (node (ref "U5") (pin "12") (pinfunction "D_12") (pintype "input"))
    )
    (net (code "104") (name "unconnected-(U5B-PRE-Pad10)") (class "Default")
      (node (ref "U5") (pin "10") (pinfunction "PRE_10") (pintype "input"))
    )
    (net (code "105") (name "unconnected-(U5B-Q-Pad9)") (class "Default")
      (node (ref "U5") (pin "9") (pinfunction "Q_9") (pintype "output"))
    )
    (net (code "106") (name "unconnected-(U5B-~{Q}-Pad8)") (class "Default")
      (node (ref "U5") (pin "8") (pinfunction "~{Q}_8") (pintype "output"))
    )
    (net (code "107") (name "Φ") (class "Default")
      (node (ref "J6") (pin "14") (pinfunction "14_14") (pintype "passive"))
      (node (ref "U5") (pin "3") (pinfunction "CLK_3") (pintype "input"))
      (node (ref "XC1") (pin "P$8") (pinfunction "X8_P$8") (pintype "bidirectional"))
    )
  )
)
